# PositiveRegulator.net
KiCad netlist of a schematic drawn in Altium Designer
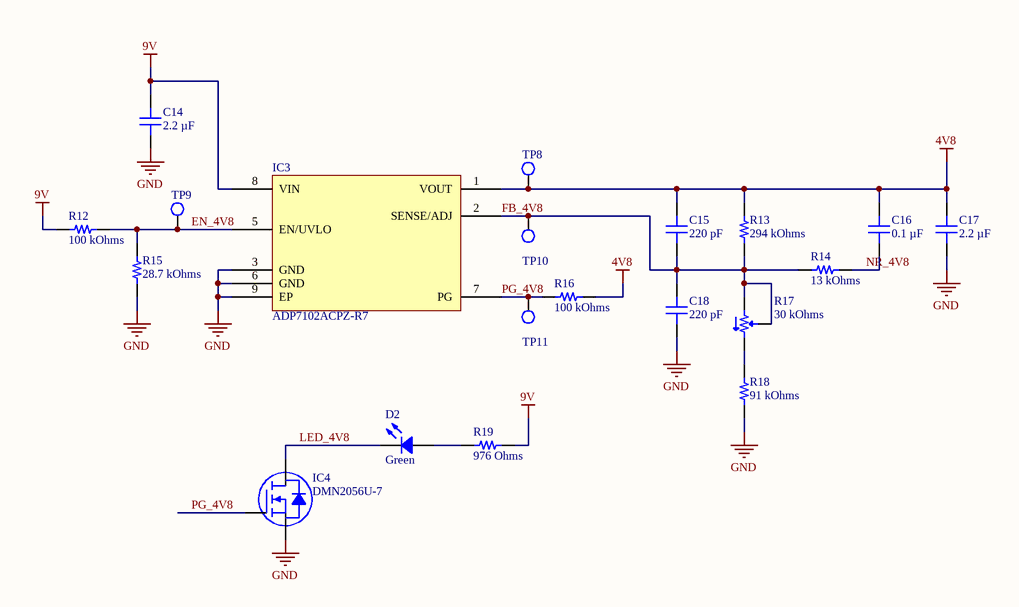
[diagram p0: PositiveRegulator.SchDoc]

(export (version "E")
  (design (tool "Eeschema 10.0.6"))
  (components
    (comp (ref "C14")
      (value "2.2 µF")
      (footprint "CAP 0805_2012")
      (description "CAP CER 2.2UF 25V X7R 0805")
      (fields
        (field (name "PART NUMBER") "GRM21BR71E225KE11L")
        (field (name "MANUFACTURER") "Murata Electronics")
      )
      (libsource (lib "altiumlibrary.com") (part "Capacitor"))
    )
    (comp (ref "C15")
      (value "220 pF")
      (footprint "CAP 0603_1608")
      (description "CAP CER 220PF 25V C0G/NPO 0603")
      (fields (field (name "PART NUMBER") "CC0603JRNPO8BN221") (field (name "MANUFACTURER") "Yageo"))
      (libsource (lib "altiumlibrary.com") (part "Capacitor"))
    )
    (comp (ref "C16")
      (value "0.1 µF")
      (footprint "CAP 0603_1608")
      (description "CAP CER 0.1UF 16V X7R 0603")
      (fields
        (field (name "PART NUMBER") "CL10B104KO8NNNC")
        (field (name "MANUFACTURER") "Samsung Electro-Mechanics")
      )
      (libsource (lib "altiumlibrary.com") (part "Capacitor"))
    )
    (comp (ref "C17")
      (value "2.2 µF")
      (footprint "CAP 0805_2012")
      (description "CAP CER 2.2UF 25V X7R 0805")
      (fields
        (field (name "PART NUMBER") "GRM21BR71E225KE11L")
        (field (name "MANUFACTURER") "Murata Electronics")
      )
      (libsource (lib "altiumlibrary.com") (part "Capacitor"))
    )
    (comp (ref "C18")
      (value "220 pF")
      (footprint "CAP 0603_1608")
      (description "CAP CER 220PF 25V C0G/NPO 0603")
      (fields (field (name "PART NUMBER") "CC0603JRNPO8BN221") (field (name "MANUFACTURER") "Yageo"))
      (libsource (lib "altiumlibrary.com") (part "Capacitor"))
    )
    (comp (ref "D2")
      (value "Green")
      (footprint "LED 0805_2012 GREEN")
      (description "LED GREEN CLEAR CHIP SMD")
      (fields (field (name "PART NUMBER") "APHCM2012CGCK-F01") (field (name "MANUFACTURER") "Kingbright"))
      (libsource (lib "altiumlibrary.com") (part "LED"))
    )
    (comp (ref "IC3")
      (value "ADP7102ACPZ-R7")
      (footprint "AD LFCSP-8 3x3MM CP-8-5")
      (description "IC REG LIN POS ADJ 300MA 8LFCSP")
      (fields (field (name "MANUFACTURER") "Analog Devices Inc."))
      (libsource (lib "altiumlibrary.com") (part "AD ADP7102ACPZ-R7"))
    )
    (comp (ref "IC4")
      (value "DMN2056U-7")
      (footprint "DIODES SOT-23-3")
      (description "MOSFET N-CHANNEL 20V 4A SOT23-3")
      (fields (field (name "MANUFACTURER") "Diodes Incorporated"))
      (libsource (lib "altiumlibrary.com") (part "DIODES INC MOSFET N-CH SOT-23-3"))
    )
    (comp (ref "R12")
      (value "100 kOhms")
      (footprint "RES 0603_1608")
      (description "RES 100K OHM 0.1% 1/5W 0603")
      (fields
        (field (name "PART NUMBER") "RS73F1JTTD1003B")
        (field (name "MANUFACTURER") "KOA Speer Electronics, Inc.")
      )
      (libsource (lib "altiumlibrary.com") (part "Resistor"))
    )
    (comp (ref "R13")
      (value "294 kOhms")
      (footprint "RES 0603_1608")
      (description "RES SMD 294K OHM 0.1% 1/10W 0603")
      (fields
        (field (name "PART NUMBER") "ERA-3AEB2943V")
        (field (name "MANUFACTURER") "Panasonic Electronic Components")
      )
      (libsource (lib "altiumlibrary.com") (part "Resistor"))
    )
    (comp (ref "R14")
      (value "13 kOhms")
      (footprint "RES 0603_1608")
      (description "RES 13K OHM 1% 1/10W 0603")
      (fields
        (field (name "PART NUMBER") "RMCF0603FT13K0")
        (field (name "MANUFACTURER") "Stackpole Electronics Inc")
      )
      (libsource (lib "altiumlibrary.com") (part "Resistor"))
    )
    (comp (ref "R15")
      (value "28.7 kOhms")
      (footprint "RES 0603_1608")
      (description "RES 28.7K OHM 1% 1/10W 0603")
      (fields (field (name "PART NUMBER") "RC0603FR-0728K7L") (field (name "MANUFACTURER") "Yageo"))
      (libsource (lib "altiumlibrary.com") (part "Resistor"))
    )
    (comp (ref "R16")
      (value "100 kOhms")
      (footprint "RES 0603_1608")
      (description "RES 100K OHM 0.1% 1/5W 0603")
      (fields
        (field (name "PART NUMBER") "RS73F1JTTD1003B")
        (field (name "MANUFACTURER") "KOA Speer Electronics, Inc.")
      )
      (libsource (lib "altiumlibrary.com") (part "Resistor"))
    )
    (comp (ref "R17")
      (value "30 kOhms")
      (footprint "POT BOURNS TRIMPOT TC33")
      (description "TRIMMER 30K OHM 0.1W J LEAD TOP")
      (fields (field (name "PART NUMBER") "TC33X-2-303E") (field (name "MANUFACTURER") "Bourns Inc."))
      (libsource (lib "altiumlibrary.com") (part "Potentiometer"))
    )
    (comp (ref "R18")
      (value "91 kOhms")
      (footprint "RES 0603_1608")
      (description "RES 91K OHM 1% 1/10W 0603")
      (fields (field (name "PART NUMBER") "RC0603FR-0791KL") (field (name "MANUFACTURER") "Yageo"))
      (libsource (lib "altiumlibrary.com") (part "Resistor"))
    )
    (comp (ref "R19")
      (value "976 Ohms")
      (footprint "RES 0805_2012")
      (description "RES 976 OHM 1% 1/8W 0805")
      (fields (field (name "PART NUMBER") "RC0805FR-07976RL") (field (name "MANUFACTURER") "Yageo"))
      (libsource (lib "altiumlibrary.com") (part "Resistor"))
    )
    (comp (ref "TP8")
      (value "Test Point")
      (footprint "TestPoint-1.5mm")
      (libsource (lib "Original Circuit") (part "Test Point"))
    )
    (comp (ref "TP9")
      (value "Test Point")
      (footprint "TestPoint-1.5mm")
      (libsource (lib "Original Circuit") (part "Test Point"))
    )
    (comp (ref "TP10")
      (value "Test Point")
      (footprint "TestPoint-1.5mm")
      (libsource (lib "Original Circuit") (part "Test Point"))
    )
    (comp (ref "TP11")
      (value "Test Point")
      (footprint "TestPoint-1.5mm")
      (libsource (lib "Original Circuit") (part "Test Point"))
    )
  )
  (nets
    (net (code "1") (name "/EN_4V8") (class "Default")
      (node (ref "IC3") (pin "5") (pinfunction "EN/UVLO_5") (pintype "passive"))
      (node (ref "R12") (pin "1") (pinfunction "1_1") (pintype "passive"))
      (node (ref "R15") (pin "2") (pinfunction "2_2") (pintype "passive"))
      (node (ref "TP9") (pin "1") (pinfunction "TP_1") (pintype "passive"))
    )
    (net (code "2") (name "/FB_4V8") (class "Default")
      (node (ref "C15") (pin "1") (pinfunction "1_1") (pintype "passive"))
      (node (ref "C18") (pin "2") (pinfunction "2_2") (pintype "passive"))
      (node (ref "IC3") (pin "2") (pinfunction "SENSE/ADJ_2") (pintype "passive"))
      (node (ref "R13") (pin "1") (pinfunction "1_1") (pintype "passive"))
      (node (ref "R14") (pin "1") (pinfunction "1_1") (pintype "passive"))
      (node (ref "R17") (pin "1") (pinfunction "1_1") (pintype "passive"))
      (node (ref "R17") (pin "2") (pinfunction "2_2") (pintype "passive"))
      (node (ref "TP10") (pin "1") (pinfunction "TP_1") (pintype "passive"))
    )
    (net (code "3") (name "/LED_4V8") (class "Default")
      (node (ref "D2") (pin "2") (pinfunction "2_2") (pintype "passive"))
      (node (ref "IC4") (pin "3") (pinfunction "D_3") (pintype "passive"))
    )
    (net (code "4") (name "/NR_4V8") (class "Default")
      (node (ref "C16") (pin "1") (pinfunction "1_1") (pintype "passive"))
      (node (ref "R14") (pin "2") (pinfunction "2_2") (pintype "passive"))
    )
    (net (code "5") (name "/PG_4V8") (class "Default")
      (node (ref "IC3") (pin "7") (pinfunction "PG_7") (pintype "passive"))
      (node (ref "IC4") (pin "1") (pinfunction "G_1") (pintype "passive"))
      (node (ref "R16") (pin "1") (pinfunction "1_1") (pintype "passive"))
      (node (ref "TP11") (pin "1") (pinfunction "TP_1") (pintype "passive"))
    )
    (net (code "6") (name "4V8") (class "Default")
      (node (ref "C15") (pin "2") (pinfunction "2_2") (pintype "passive"))
      (node (ref "C16") (pin "2") (pinfunction "2_2") (pintype "passive"))
      (node (ref "C17") (pin "2") (pinfunction "2_2") (pintype "passive"))
      (node (ref "IC3") (pin "1") (pinfunction "VOUT_1") (pintype "passive"))
      (node (ref "R13") (pin "2") (pinfunction "2_2") (pintype "passive"))
      (node (ref "R16") (pin "2") (pinfunction "2_2") (pintype "passive"))
      (node (ref "TP8") (pin "1") (pinfunction "TP_1") (pintype "passive"))
    )
    (net (code "7") (name "9V") (class "Default")
      (node (ref "C14") (pin "2") (pinfunction "2_2") (pintype "passive"))
      (node (ref "IC3") (pin "8") (pinfunction "VIN_8") (pintype "passive"))
      (node (ref "R12") (pin "2") (pinfunction "2_2") (pintype "passive"))
      (node (ref "R19") (pin "2") (pinfunction "2_2") (pintype "passive"))
    )
    (net (code "8") (name "GND") (class "Default")
      (node (ref "C14") (pin "1") (pinfunction "1_1") (pintype "passive"))
      (node (ref "C17") (pin "1") (pinfunction "1_1") (pintype "passive"))
      (node (ref "C18") (pin "1") (pinfunction "1_1") (pintype "passive"))
      (node (ref "IC3") (pin "3") (pinfunction "GND_3") (pintype "passive"))
      (node (ref "IC3") (pin "6") (pinfunction "GND_6") (pintype "passive"))
      (node (ref "IC3") (pin "9") (pinfunction "EP_9") (pintype "passive"))
      (node (ref "IC4") (pin "2") (pinfunction "S_2") (pintype "passive"))
      (node (ref "R15") (pin "1") (pinfunction "1_1") (pintype "passive"))
      (node (ref "R18") (pin "1") (pinfunction "1_1") (pintype "passive"))
    )
    (net (code "9") (name "Net-(D2-Pad1)") (class "Default")
      (node (ref "D2") (pin "1") (pinfunction "1_1") (pintype "passive"))
      (node (ref "R19") (pin "1") (pinfunction "1_1") (pintype "passive"))
    )
    (net (code "10") (name "Net-(R17-Pad3)") (class "Default")
      (node (ref "R17") (pin "3") (pinfunction "3_3") (pintype "passive"))
      (node (ref "R18") (pin "2") (pinfunction "2_2") (pintype "passive"))
    )
  )
)
